# 32u4_Gripper_2015_A.net
KiCad netlist of a schematic drawn in EAGLE
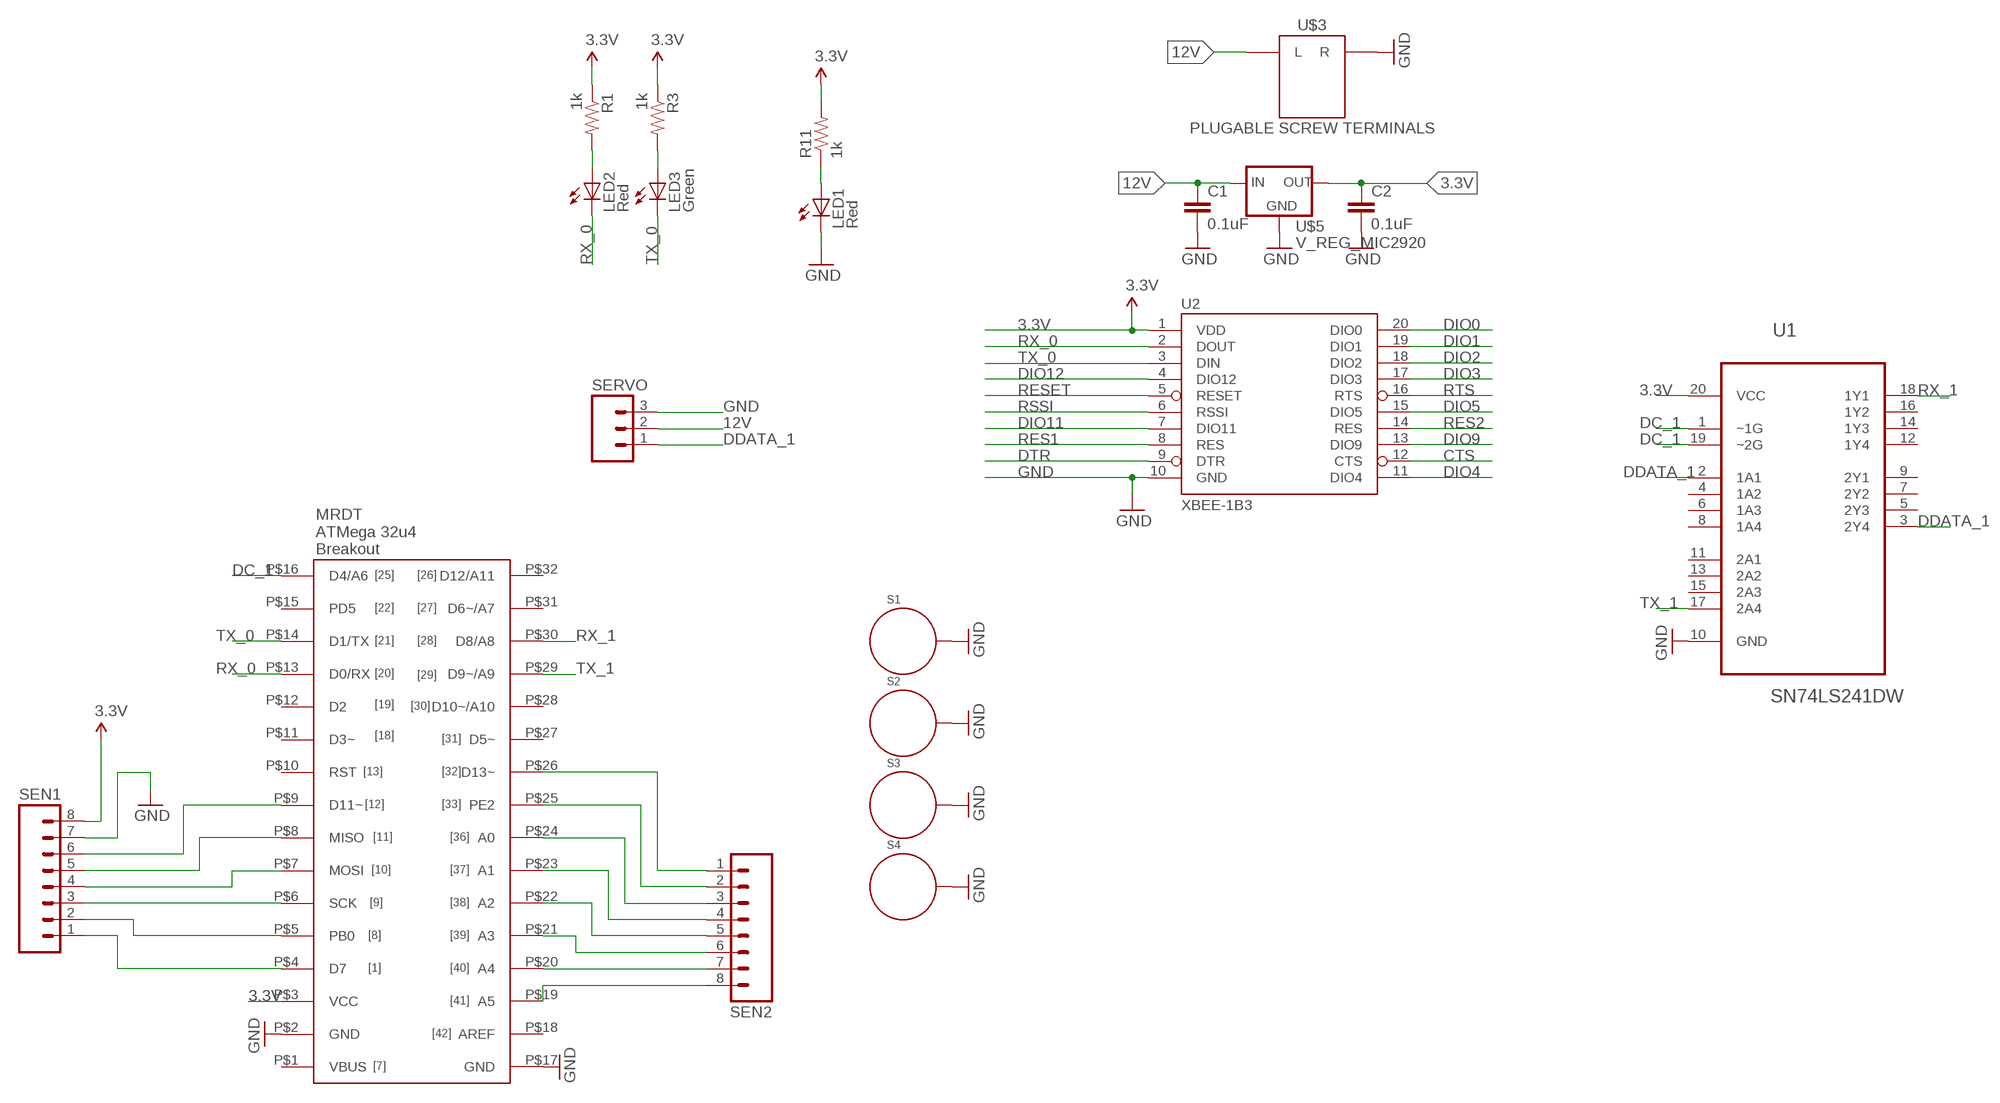
[diagram p0: schematic, sheet 1]

(export (version "E")
  (design (tool "Eeschema 10.0.6"))
  (components
    (comp (ref "C1")
      (value "0.1uF")
      (footprint "eagle-import:1206")
      (libsource (lib "eagle-import") (part "CAP1206"))
    )
    (comp (ref "C2")
      (value "0.1uF")
      (footprint "eagle-import:1206")
      (libsource (lib "eagle-import") (part "CAP1206"))
    )
    (comp (ref "LED1")
      (value "Red")
      (footprint "eagle-import:LED-0603")
      (libsource (lib "eagle-import") (part "LED0603"))
    )
    (comp (ref "LED2")
      (value "Red")
      (footprint "eagle-import:LED-0603")
      (libsource (lib "eagle-import") (part "LED0603"))
    )
    (comp (ref "LED3")
      (value "Green")
      (footprint "eagle-import:LED-0603")
      (libsource (lib "eagle-import") (part "LED0603"))
    )
    (comp (ref "R1")
      (value "1k")
      (footprint "eagle-import:1206")
      (libsource (lib "eagle-import") (part "RESISTOR1206"))
    )
    (comp (ref "R3")
      (value "1k")
      (footprint "eagle-import:1206")
      (libsource (lib "eagle-import") (part "RESISTOR1206"))
    )
    (comp (ref "R11")
      (value "1k")
      (footprint "eagle-import:1206")
      (libsource (lib "eagle-import") (part "RESISTOR1206"))
    )
    (comp (ref "S1")
      (value "STANDOFF_ELECTRICAL")
      (footprint "eagle-import:STANDOFF-ELECTRICAL")
      (libsource (lib "eagle-import") (part "STANDOFF_ELECTRICAL"))
    )
    (comp (ref "S2")
      (value "STANDOFF_ELECTRICAL")
      (footprint "eagle-import:STANDOFF-ELECTRICAL")
      (libsource (lib "eagle-import") (part "STANDOFF_ELECTRICAL"))
    )
    (comp (ref "S3")
      (value "STANDOFF_ELECTRICAL")
      (footprint "eagle-import:STANDOFF-ELECTRICAL")
      (libsource (lib "eagle-import") (part "STANDOFF_ELECTRICAL"))
    )
    (comp (ref "S4")
      (value "STANDOFF_ELECTRICAL")
      (footprint "eagle-import:STANDOFF-ELECTRICAL")
      (libsource (lib "eagle-import") (part "STANDOFF_ELECTRICAL"))
    )
    (comp (ref "SEN1")
      (value "M081X08")
      (footprint "eagle-import:1X08")
      (libsource (lib "eagle-import") (part "M081X08"))
    )
    (comp (ref "SEN2")
      (value "M081X08")
      (footprint "eagle-import:1X08")
      (libsource (lib "eagle-import") (part "M081X08"))
    )
    (comp (ref "SERVO")
      (value "M03PTH")
      (footprint "eagle-import:1X03")
      (libsource (lib "eagle-import") (part "M03PTH"))
    )
    (comp (ref "U$1")
      (value "32U4_BREAKOU_SMD")
      (footprint "eagle-import:32U3_MCU_DIP_SMD")
      (libsource (lib "eagle-import") (part "32U4_BREAKOU_SMD"))
    )
    (comp (ref "U$3")
      (value "PLUGABLE SCREW TERMINALS")
      (footprint "eagle-import:691321100002")
      (libsource (lib "eagle-import") (part "H_WR-TBL_3210002VERT"))
    )
    (comp (ref "U$5")
      (value "V_REG_MIC2920")
      (footprint "eagle-import:SOT223")
      (libsource (lib "eagle-import") (part "V_REG_MIC2920"))
    )
    (comp (ref "U1")
      (value "SN74LS241DW")
      (footprint "eagle-import:SOIC127P1030X265-20N")
      (libsource (lib "eagle-import") (part "SN74LS241DW"))
    )
    (comp (ref "U2")
      (value "XBEE-1B3")
      (footprint "eagle-import:XBEE-SMD")
      (libsource (lib "eagle-import") (part "XBEE-1B3"))
    )
  )
  (nets
    (net (code "1") (name "/CTS") (class "Default")
      (node (ref "U2") (pin "12") (pinfunction "CTS_12") (pintype "output"))
    )
    (net (code "2") (name "/DC_1") (class "Default")
      (node (ref "U$1") (pin "P$16") (pinfunction "D4/A6_P$16") (pintype "bidirectional"))
      (node (ref "U1") (pin "1") (pinfunction "~{1G}_1") (pintype "input"))
      (node (ref "U1") (pin "19") (pinfunction "~{2G}_19") (pintype "input"))
    )
    (net (code "3") (name "/DDATA_1") (class "Default")
      (node (ref "SERVO") (pin "1") (pinfunction "1_1") (pintype "passive"))
      (node (ref "U1") (pin "2") (pinfunction "1A1_2") (pintype "input"))
      (node (ref "U1") (pin "3") (pinfunction "2Y4_3") (pintype "output"))
    )
    (net (code "4") (name "/DIO0") (class "Default")
      (node (ref "U2") (pin "20") (pinfunction "DIO0_20") (pintype "bidirectional"))
    )
    (net (code "5") (name "/DIO1") (class "Default")
      (node (ref "U2") (pin "19") (pinfunction "DIO1_19") (pintype "bidirectional"))
    )
    (net (code "6") (name "/DIO2") (class "Default")
      (node (ref "U2") (pin "18") (pinfunction "DIO2_18") (pintype "bidirectional"))
    )
    (net (code "7") (name "/DIO3") (class "Default")
      (node (ref "U2") (pin "17") (pinfunction "DIO3_17") (pintype "bidirectional"))
    )
    (net (code "8") (name "/DIO4") (class "Default")
      (node (ref "U2") (pin "11") (pinfunction "DIO4_11") (pintype "bidirectional"))
    )
    (net (code "9") (name "/DIO5") (class "Default")
      (node (ref "U2") (pin "15") (pinfunction "DIO5_15") (pintype "bidirectional"))
    )
    (net (code "10") (name "/DIO9") (class "Default")
      (node (ref "U2") (pin "13") (pinfunction "DIO9_13") (pintype "bidirectional"))
    )
    (net (code "11") (name "/DIO11") (class "Default")
      (node (ref "U2") (pin "7") (pinfunction "DIO11_7") (pintype "bidirectional"))
    )
    (net (code "12") (name "/DIO12") (class "Default")
      (node (ref "U2") (pin "4") (pinfunction "DIO12_4") (pintype "bidirectional"))
    )
    (net (code "13") (name "/DTR") (class "Default")
      (node (ref "U2") (pin "9") (pinfunction "DTR_9") (pintype "bidirectional"))
    )
    (net (code "14") (name "/RES1") (class "Default")
      (node (ref "U2") (pin "8") (pinfunction "RES_8") (pintype "bidirectional"))
    )
    (net (code "15") (name "/RES2") (class "Default")
      (node (ref "U2") (pin "14") (pinfunction "RES_14") (pintype "bidirectional"))
    )
    (net (code "16") (name "/RESET") (class "Default")
      (node (ref "U2") (pin "5") (pinfunction "RESET_5") (pintype "input"))
    )
    (net (code "17") (name "/RSSI") (class "Default")
      (node (ref "U2") (pin "6") (pinfunction "RSSI_6") (pintype "bidirectional"))
    )
    (net (code "18") (name "/RTS") (class "Default")
      (node (ref "U2") (pin "16") (pinfunction "RTS_16") (pintype "input"))
    )
    (net (code "19") (name "/RX_0") (class "Default")
      (node (ref "LED2") (pin "C") (pinfunction "C_C") (pintype "passive"))
      (node (ref "U$1") (pin "P$13") (pinfunction "D0/RX_P$13") (pintype "bidirectional"))
      (node (ref "U2") (pin "2") (pinfunction "DOUT_2") (pintype "output"))
    )
    (net (code "20") (name "/RX_1") (class "Default")
      (node (ref "U$1") (pin "P$30") (pinfunction "D8/A8_P$30") (pintype "bidirectional"))
      (node (ref "U1") (pin "18") (pinfunction "1Y1_18") (pintype "output"))
    )
    (net (code "21") (name "/TX_0") (class "Default")
      (node (ref "LED3") (pin "C") (pinfunction "C_C") (pintype "passive"))
      (node (ref "U$1") (pin "P$14") (pinfunction "D1/TX_P$14") (pintype "bidirectional"))
      (node (ref "U2") (pin "3") (pinfunction "DIN_3") (pintype "input"))
    )
    (net (code "22") (name "/TX_1") (class "Default")
      (node (ref "U$1") (pin "P$29") (pinfunction "D9~{/A9}_P$29") (pintype "bidirectional"))
      (node (ref "U1") (pin "17") (pinfunction "2A4_17") (pintype "input"))
    )
    (net (code "23") (name "3.3V") (class "Default")
      (node (ref "C2") (pin "1") (pinfunction "1_1") (pintype "passive"))
      (node (ref "R1") (pin "1") (pinfunction "1_1") (pintype "passive"))
      (node (ref "R11") (pin "2") (pinfunction "2_2") (pintype "passive"))
      (node (ref "R3") (pin "1") (pinfunction "1_1") (pintype "passive"))
      (node (ref "SEN1") (pin "8") (pinfunction "8_8") (pintype "passive"))
      (node (ref "U$1") (pin "P$3") (pinfunction "VCC_P$3") (pintype "bidirectional"))
      (node (ref "U$5") (pin "3") (pinfunction "OUT_3") (pintype "output"))
      (node (ref "U1") (pin "20") (pinfunction "VCC_20") (pintype "power_in"))
      (node (ref "U2") (pin "1") (pinfunction "VDD_1") (pintype "power_in"))
    )
    (net (code "24") (name "12V") (class "Default")
      (node (ref "C1") (pin "1") (pinfunction "1_1") (pintype "passive"))
      (node (ref "SERVO") (pin "2") (pinfunction "2_2") (pintype "passive"))
      (node (ref "U$3") (pin "L") (pinfunction "L_L") (pintype "bidirectional"))
      (node (ref "U$5") (pin "1") (pinfunction "IN_1") (pintype "input"))
    )
    (net (code "25") (name "GND") (class "Default")
      (node (ref "C1") (pin "2") (pinfunction "2_2") (pintype "passive"))
      (node (ref "C2") (pin "2") (pinfunction "2_2") (pintype "passive"))
      (node (ref "LED1") (pin "C") (pinfunction "C_C") (pintype "passive"))
      (node (ref "S1") (pin "P1") (pinfunction "P$1_P1") (pintype "bidirectional"))
      (node (ref "S2") (pin "P1") (pinfunction "P$1_P1") (pintype "bidirectional"))
      (node (ref "S3") (pin "P1") (pinfunction "P$1_P1") (pintype "bidirectional"))
      (node (ref "S4") (pin "P1") (pinfunction "P$1_P1") (pintype "bidirectional"))
      (node (ref "SEN1") (pin "7") (pinfunction "7_7") (pintype "passive"))
      (node (ref "SERVO") (pin "3") (pinfunction "3_3") (pintype "passive"))
      (node (ref "U$1") (pin "P$17") (pinfunction "GND_P$17") (pintype "bidirectional"))
      (node (ref "U$1") (pin "P$2") (pinfunction "GND_P$2") (pintype "bidirectional"))
      (node (ref "U$3") (pin "R") (pinfunction "R_R") (pintype "bidirectional"))
      (node (ref "U$5") (pin "2") (pinfunction "GND_2") (pintype "input"))
      (node (ref "U$5") (pin "4") (pinfunction "GND_4") (pintype "input"))
      (node (ref "U1") (pin "10") (pinfunction "GND_10") (pintype "passive"))
      (node (ref "U2") (pin "10") (pinfunction "GND_10") (pintype "power_in"))
    )
    (net (code "26") (name "Net-(LED1-PadA)") (class "Default")
      (node (ref "LED1") (pin "A") (pinfunction "A_A") (pintype "passive"))
      (node (ref "R11") (pin "1") (pinfunction "1_1") (pintype "passive"))
    )
    (net (code "27") (name "Net-(LED2-PadA)") (class "Default")
      (node (ref "LED2") (pin "A") (pinfunction "A_A") (pintype "passive"))
      (node (ref "R1") (pin "2") (pinfunction "2_2") (pintype "passive"))
    )
    (net (code "28") (name "Net-(LED3-PadA)") (class "Default")
      (node (ref "LED3") (pin "A") (pinfunction "A_A") (pintype "passive"))
      (node (ref "R3") (pin "2") (pinfunction "2_2") (pintype "passive"))
    )
    (net (code "29") (name "Net-(U$1-A0)") (class "Default")
      (node (ref "SEN2") (pin "3") (pinfunction "3_3") (pintype "passive"))
      (node (ref "U$1") (pin "P$24") (pinfunction "A0_P$24") (pintype "bidirectional"))
    )
    (net (code "30") (name "Net-(U$1-A1)") (class "Default")
      (node (ref "SEN2") (pin "4") (pinfunction "4_4") (pintype "passive"))
      (node (ref "U$1") (pin "P$23") (pinfunction "A1_P$23") (pintype "bidirectional"))
    )
    (net (code "31") (name "Net-(U$1-A2)") (class "Default")
      (node (ref "SEN2") (pin "5") (pinfunction "5_5") (pintype "passive"))
      (node (ref "U$1") (pin "P$22") (pinfunction "A2_P$22") (pintype "bidirectional"))
    )
    (net (code "32") (name "Net-(U$1-A3)") (class "Default")
      (node (ref "SEN2") (pin "6") (pinfunction "6_6") (pintype "passive"))
      (node (ref "U$1") (pin "P$21") (pinfunction "A3_P$21") (pintype "bidirectional"))
    )
    (net (code "33") (name "Net-(U$1-A4)") (class "Default")
      (node (ref "SEN2") (pin "7") (pinfunction "7_7") (pintype "passive"))
      (node (ref "U$1") (pin "P$20") (pinfunction "A4_P$20") (pintype "bidirectional"))
    )
    (net (code "34") (name "Net-(U$1-A5)") (class "Default")
      (node (ref "SEN2") (pin "8") (pinfunction "8_8") (pintype "passive"))
      (node (ref "U$1") (pin "P$19") (pinfunction "A5_P$19") (pintype "bidirectional"))
    )
    (net (code "35") (name "Net-(U$1-D7)") (class "Default")
      (node (ref "SEN1") (pin "1") (pinfunction "1_1") (pintype "passive"))
      (node (ref "U$1") (pin "P$4") (pinfunction "D7_P$4") (pintype "bidirectional"))
    )
    (net (code "36") (name "Net-(U$1-D11~{})") (class "Default")
      (node (ref "SEN1") (pin "6") (pinfunction "6_6") (pintype "passive"))
      (node (ref "U$1") (pin "P$9") (pinfunction "D11~{}_P$9") (pintype "bidirectional"))
    )
    (net (code "37") (name "Net-(U$1-D13~{})") (class "Default")
      (node (ref "SEN2") (pin "1") (pinfunction "1_1") (pintype "passive"))
      (node (ref "U$1") (pin "P$26") (pinfunction "D13~{}_P$26") (pintype "bidirectional"))
    )
    (net (code "38") (name "Net-(U$1-MISO)") (class "Default")
      (node (ref "SEN1") (pin "5") (pinfunction "5_5") (pintype "passive"))
      (node (ref "U$1") (pin "P$8") (pinfunction "MISO_P$8") (pintype "bidirectional"))
    )
    (net (code "39") (name "Net-(U$1-MOSI)") (class "Default")
      (node (ref "SEN1") (pin "4") (pinfunction "4_4") (pintype "passive"))
      (node (ref "U$1") (pin "P$7") (pinfunction "MOSI_P$7") (pintype "bidirectional"))
    )
    (net (code "40") (name "Net-(U$1-PB0)") (class "Default")
      (node (ref "SEN1") (pin "2") (pinfunction "2_2") (pintype "passive"))
      (node (ref "U$1") (pin "P$5") (pinfunction "PB0_P$5") (pintype "bidirectional"))
    )
    (net (code "41") (name "Net-(U$1-PE2)") (class "Default")
      (node (ref "SEN2") (pin "2") (pinfunction "2_2") (pintype "passive"))
      (node (ref "U$1") (pin "P$25") (pinfunction "PE2_P$25") (pintype "bidirectional"))
    )
    (net (code "42") (name "Net-(U$1-SCK)") (class "Default")
      (node (ref "SEN1") (pin "3") (pinfunction "3_3") (pintype "passive"))
      (node (ref "U$1") (pin "P$6") (pinfunction "SCK_P$6") (pintype "bidirectional"))
    )
    (net (code "43") (name "unconnected-(U$1-AREF-PadP$18)") (class "Default")
      (node (ref "U$1") (pin "P$18") (pinfunction "AREF_P$18") (pintype "bidirectional"))
    )
    (net (code "44") (name "unconnected-(U$1-D2-PadP$12)") (class "Default")
      (node (ref "U$1") (pin "P$12") (pinfunction "D2_P$12") (pintype "bidirectional"))
    )
    (net (code "45") (name "unconnected-(U$1-D3~{}-PadP$11)") (class "Default")
      (node (ref "U$1") (pin "P$11") (pinfunction "D3~{}_P$11") (pintype "bidirectional"))
    )
    (net (code "46") (name "unconnected-(U$1-D5~{}-PadP$27)") (class "Default")
      (node (ref "U$1") (pin "P$27") (pinfunction "D5~{}_P$27") (pintype "bidirectional"))
    )
    (net (code "47") (name "unconnected-(U$1-D6~{{slash}A7}-PadP$31)") (class "Default")
      (node (ref "U$1") (pin "P$31") (pinfunction "D6~{/A7}_P$31") (pintype "bidirectional"))
    )
    (net (code "48") (name "unconnected-(U$1-D10~{{slash}A10}-PadP$28)") (class "Default")
      (node (ref "U$1") (pin "P$28") (pinfunction "D10~{/A10}_P$28") (pintype "bidirectional"))
    )
    (net (code "49") (name "unconnected-(U$1-D12{slash}A11-PadP$32)") (class "Default")
      (node (ref "U$1") (pin "P$32") (pinfunction "D12/A11_P$32") (pintype "bidirectional"))
    )
    (net (code "50") (name "unconnected-(U$1-PD5-PadP$15)") (class "Default")
      (node (ref "U$1") (pin "P$15") (pinfunction "PD5_P$15") (pintype "bidirectional"))
    )
    (net (code "51") (name "unconnected-(U$1-RST-PadP$10)") (class "Default")
      (node (ref "U$1") (pin "P$10") (pinfunction "RST_P$10") (pintype "bidirectional"))
    )
    (net (code "52") (name "unconnected-(U$1-VBUS-PadP$1)") (class "Default")
      (node (ref "U$1") (pin "P$1") (pinfunction "VBUS_P$1") (pintype "bidirectional"))
    )
    (net (code "53") (name "unconnected-(U1-1A2-Pad4)") (class "Default")
      (node (ref "U1") (pin "4") (pinfunction "1A2_4") (pintype "input"))
    )
    (net (code "54") (name "unconnected-(U1-1A3-Pad6)") (class "Default")
      (node (ref "U1") (pin "6") (pinfunction "1A3_6") (pintype "input"))
    )
    (net (code "55") (name "unconnected-(U1-1A4-Pad8)") (class "Default")
      (node (ref "U1") (pin "8") (pinfunction "1A4_8") (pintype "input"))
    )
    (net (code "56") (name "unconnected-(U1-1Y2-Pad16)") (class "Default")
      (node (ref "U1") (pin "16") (pinfunction "1Y2_16") (pintype "output"))
    )
    (net (code "57") (name "unconnected-(U1-1Y3-Pad14)") (class "Default")
      (node (ref "U1") (pin "14") (pinfunction "1Y3_14") (pintype "output"))
    )
    (net (code "58") (name "unconnected-(U1-1Y4-Pad12)") (class "Default")
      (node (ref "U1") (pin "12") (pinfunction "1Y4_12") (pintype "output"))
    )
    (net (code "59") (name "unconnected-(U1-2A1-Pad11)") (class "Default")
      (node (ref "U1") (pin "11") (pinfunction "2A1_11") (pintype "input"))
    )
    (net (code "60") (name "unconnected-(U1-2A2-Pad13)") (class "Default")
      (node (ref "U1") (pin "13") (pinfunction "2A2_13") (pintype "input"))
    )
    (net (code "61") (name "unconnected-(U1-2A3-Pad15)") (class "Default")
      (node (ref "U1") (pin "15") (pinfunction "2A3_15") (pintype "input"))
    )
    (net (code "62") (name "unconnected-(U1-2Y1-Pad9)") (class "Default")
      (node (ref "U1") (pin "9") (pinfunction "2Y1_9") (pintype "output"))
    )
    (net (code "63") (name "unconnected-(U1-2Y2-Pad7)") (class "Default")
      (node (ref "U1") (pin "7") (pinfunction "2Y2_7") (pintype "output"))
    )
    (net (code "64") (name "unconnected-(U1-2Y3-Pad5)") (class "Default")
      (node (ref "U1") (pin "5") (pinfunction "2Y3_5") (pintype "output"))
    )
  )
)
